# Solenoid_16.net
KiCad netlist of a schematic drawn in EAGLE
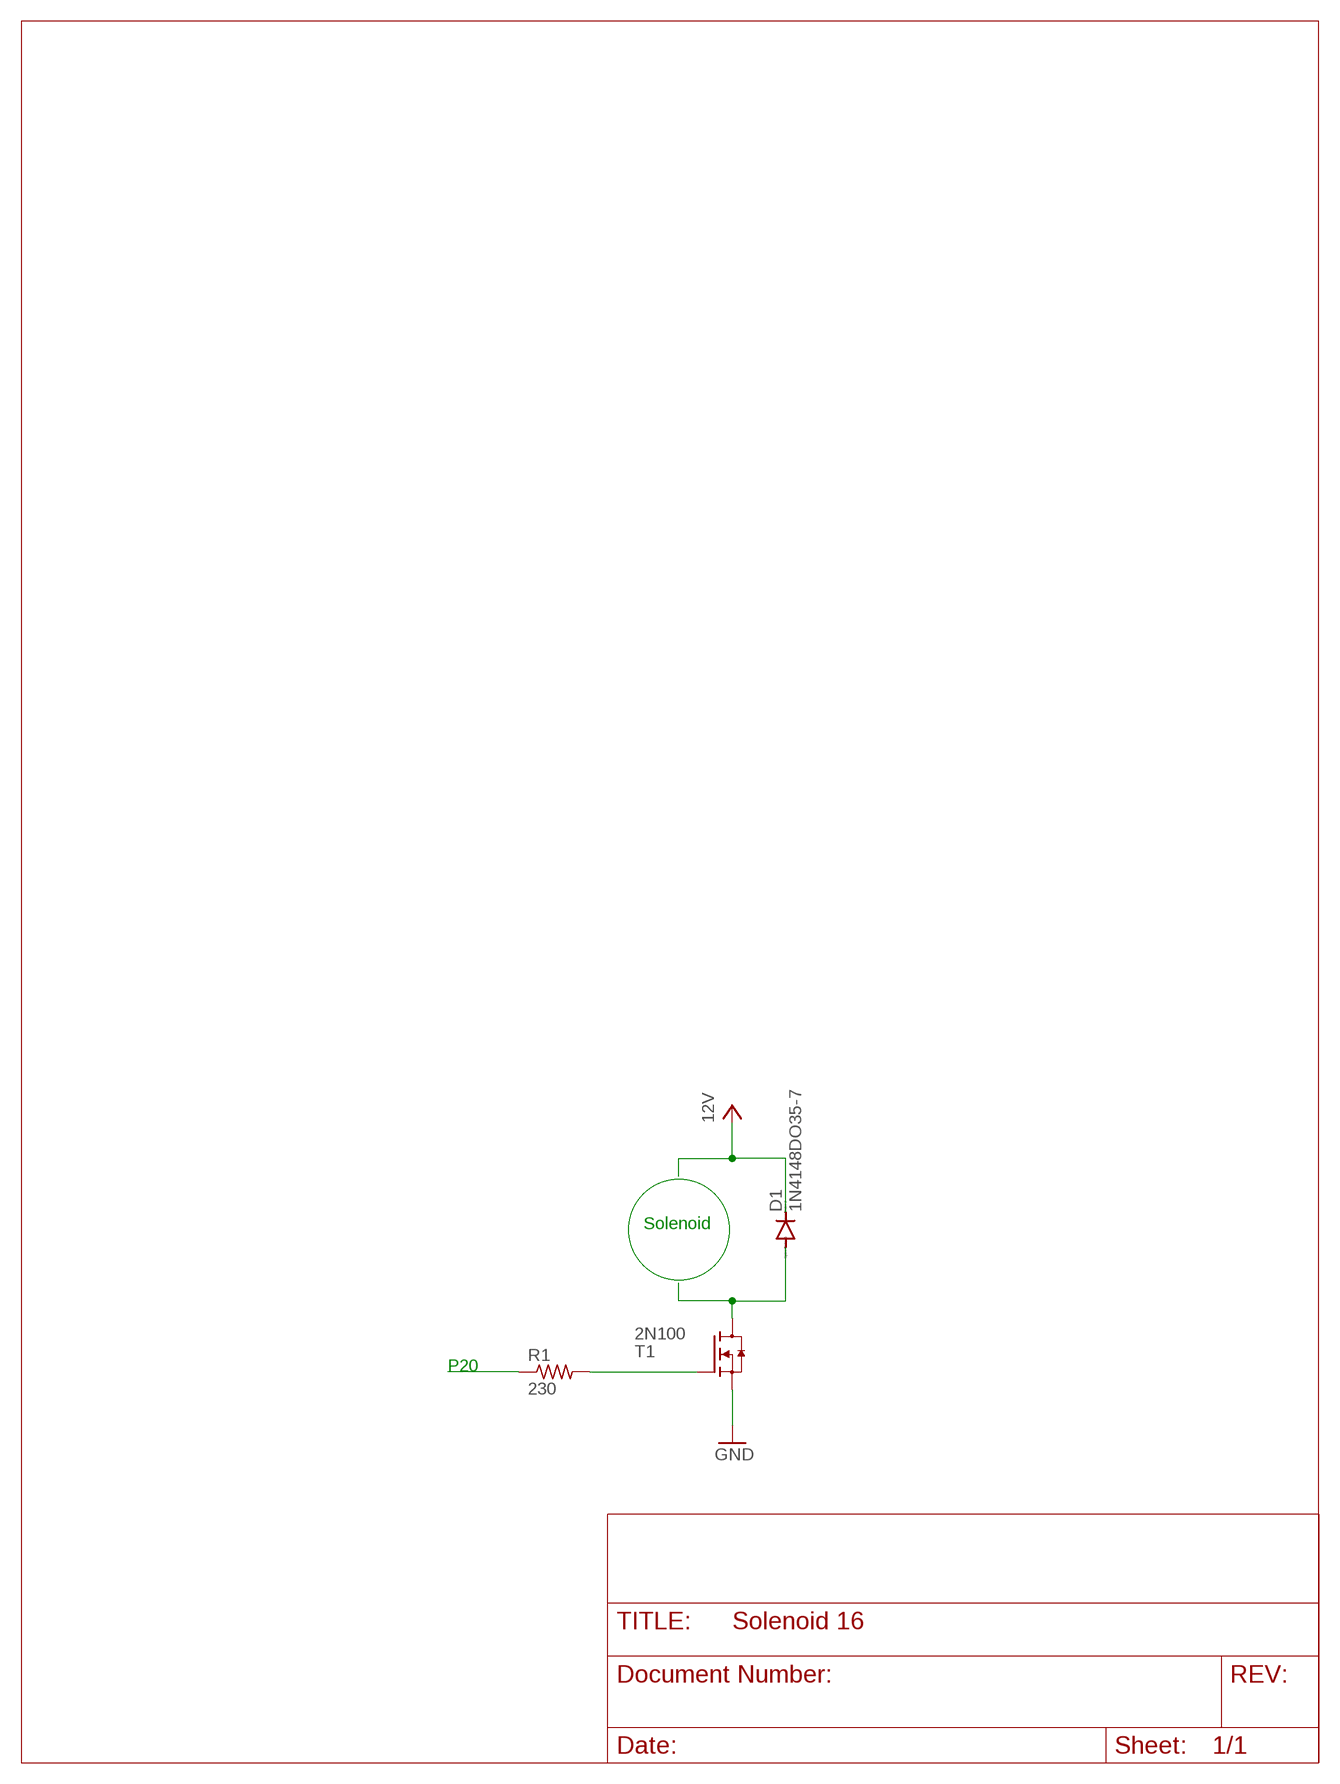
[diagram p0: schematic, sheet 1]

(export (version "E")
  (design (tool "Eeschema 10.0.6"))
  (components
    (comp (ref "D1")
      (value "1N4148DO35-7")
      (footprint "eagle-import:DO35-7")
      (libsource (lib "eagle-import") (part "1N4148DO35-7"))
    )
    (comp (ref "R1")
      (value "230")
      (footprint "eagle-import:0204_7")
      (libsource (lib "eagle-import") (part "R-US_0204/7"))
    )
    (comp (ref "T1")
      (value "2N100")
      (footprint "eagle-import:PG-TO263-7-3")
      (libsource (lib "eagle-import") (part "IPB180N06S4-H1"))
    )
  )
  (nets
    (net (code "1") (name "12V") (class "Default")
      (node (ref "D1") (pin "C") (pinfunction "C_C") (pintype "passive"))
    )
    (net (code "2") (name "GND") (class "Default")
      (node (ref "T1") (pin "2") (pinfunction "S_2") (pintype "passive"))
      (node (ref "T1") (pin "3") (pinfunction "S_3") (pintype "passive"))
      (node (ref "T1") (pin "5") (pinfunction "S_5") (pintype "passive"))
      (node (ref "T1") (pin "6") (pinfunction "S_6") (pintype "passive"))
      (node (ref "T1") (pin "7") (pinfunction "S_7") (pintype "passive"))
    )
    (net (code "3") (name "Net-(T1-D)") (class "Default")
      (node (ref "D1") (pin "A") (pinfunction "A_A") (pintype "passive"))
      (node (ref "T1") (pin "8") (pinfunction "D_8") (pintype "passive"))
    )
    (net (code "4") (name "Net-(T1-G)") (class "Default")
      (node (ref "R1") (pin "2") (pinfunction "2_2") (pintype "passive"))
      (node (ref "T1") (pin "1") (pinfunction "G_1") (pintype "passive"))
    )
    (net (code "5") (name "unconnected-(R1-Pad1)") (class "Default")
      (node (ref "R1") (pin "1") (pinfunction "1_1") (pintype "passive"))
    )
  )
)
